# f-91ksd_r0.net
KiCad netlist of a schematic drawn in EAGLE
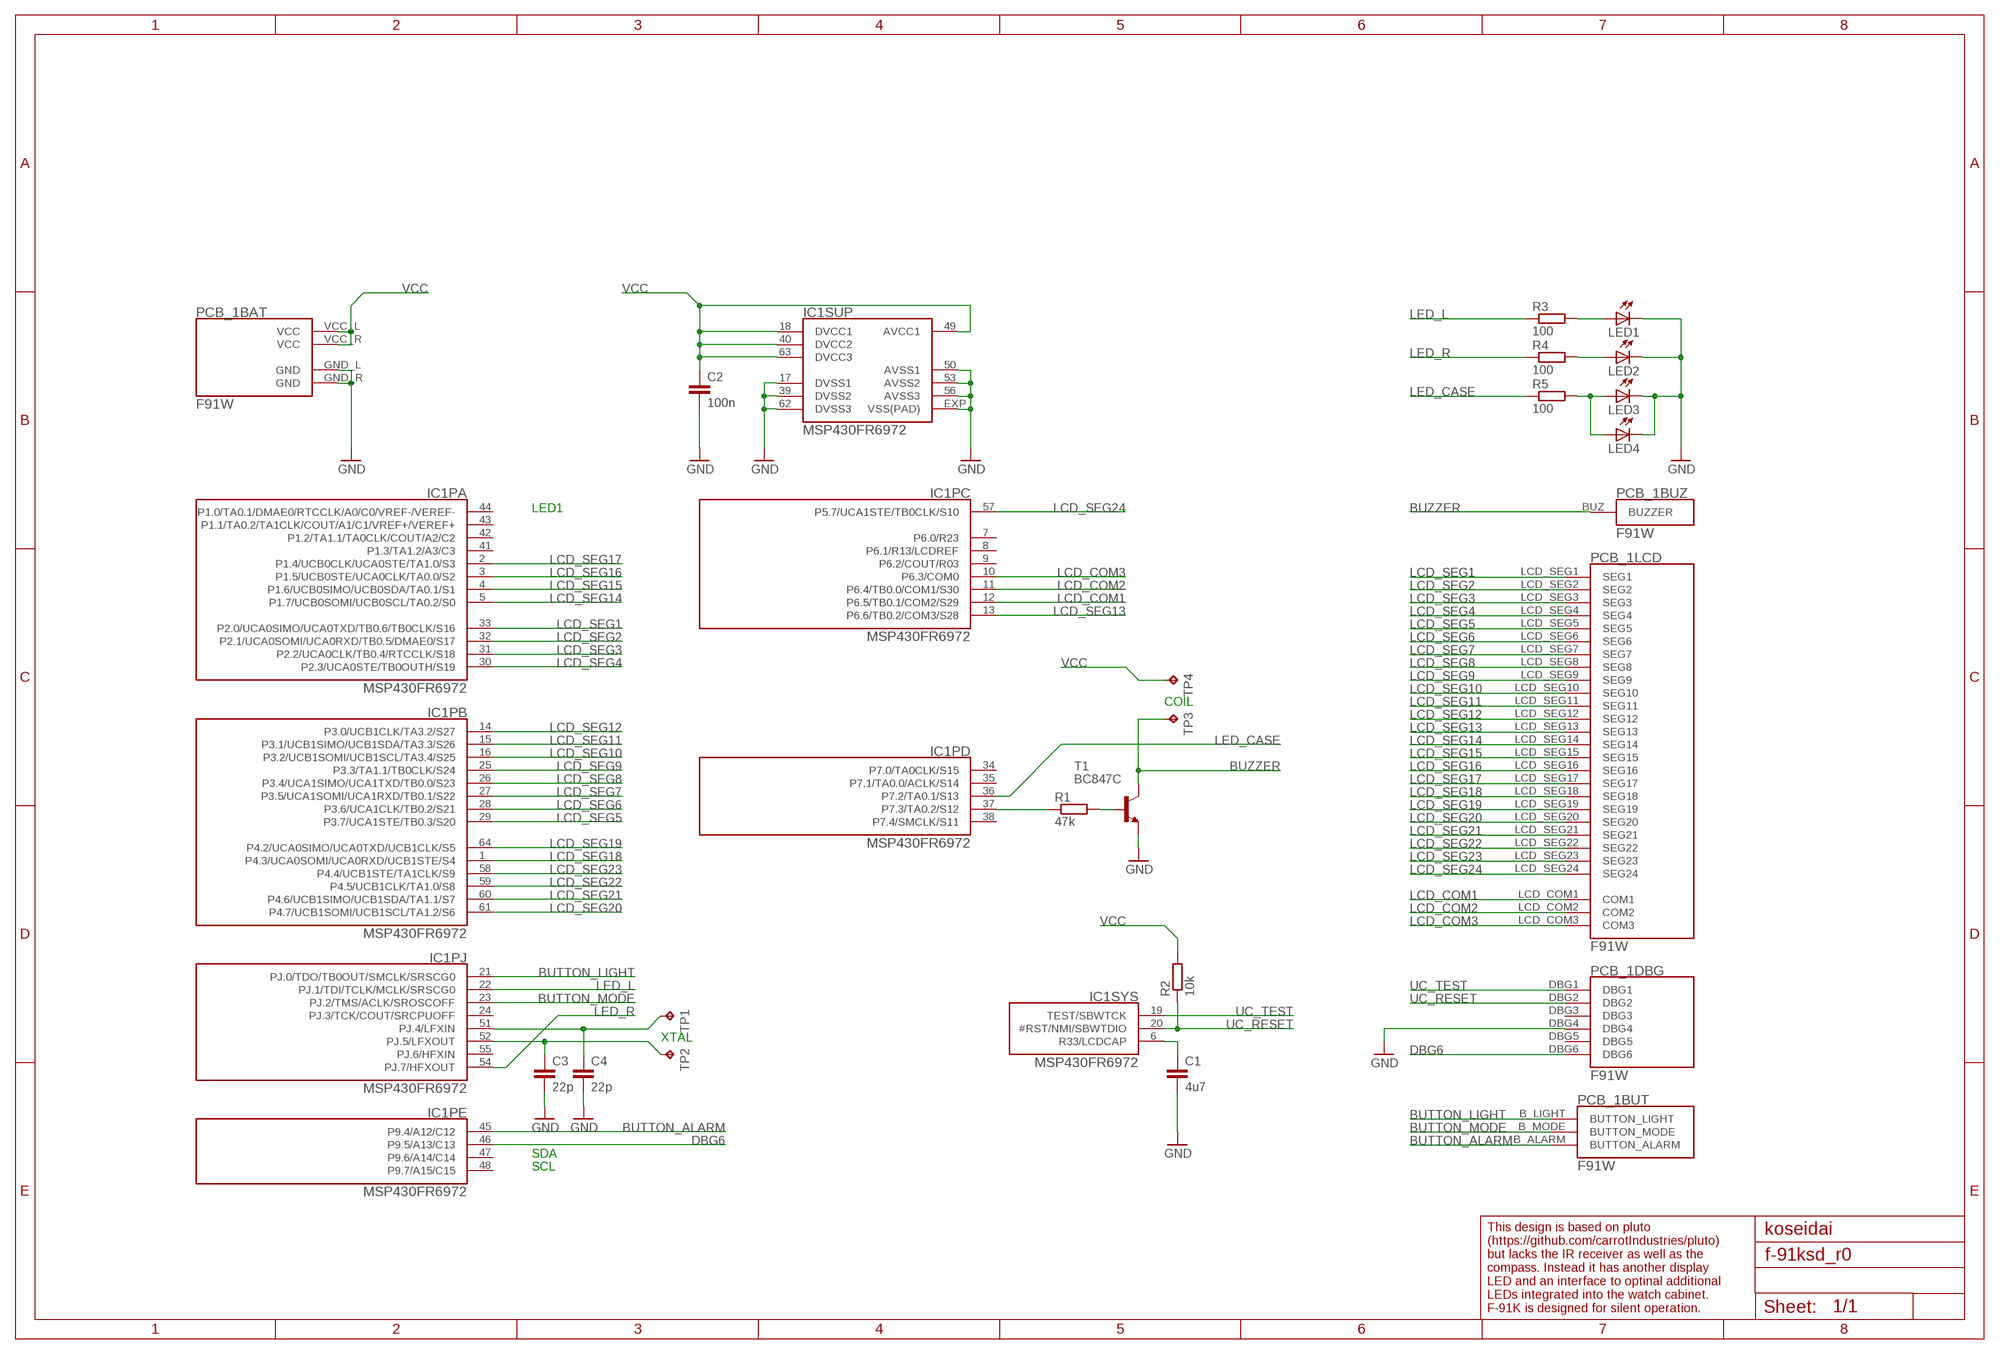
[diagram p0: schematic, sheet 1]

(export (version "E")
  (design (tool "Eeschema 10.0.6"))
  (components
    (comp (ref "C1")
      (value "4u7")
      (footprint "eagle-import:C0603-WW")
      (libsource (lib "eagle-import") (part "C-EUC0603-WW"))
    )
    (comp (ref "C2")
      (value "100n")
      (footprint "eagle-import:C0603-WW")
      (libsource (lib "eagle-import") (part "C-EUC0603-WW"))
    )
    (comp (ref "C3")
      (value "22p")
      (footprint "eagle-import:C0603-WW")
      (libsource (lib "eagle-import") (part "C-EUC0603-WW"))
    )
    (comp (ref "C4")
      (value "22p")
      (footprint "eagle-import:C0603-WW")
      (libsource (lib "eagle-import") (part "C-EUC0603-WW"))
    )
    (comp (ref "IC1")
      (value "MSP430FR6972")
      (footprint "eagle-import:QFN64-9X9")
      (libsource (lib "eagle-import") (part "MSP430FR6972"))
    )
    (comp (ref "LED1")
      (value "LEDCHIPLED_0805")
      (footprint "eagle-import:CHIPLED_0805")
      (libsource (lib "eagle-import") (part "LEDCHIPLED_0805"))
    )
    (comp (ref "LED2")
      (value "LEDCHIPLED_0805")
      (footprint "eagle-import:CHIPLED_0805")
      (libsource (lib "eagle-import") (part "LEDCHIPLED_0805"))
    )
    (comp (ref "LED3")
      (value "LEDCHIPLED_0603")
      (footprint "eagle-import:CHIPLED_0603")
      (libsource (lib "eagle-import") (part "LEDCHIPLED_0603"))
    )
    (comp (ref "LED4")
      (value "LEDCHIPLED_0603")
      (footprint "eagle-import:CHIPLED_0603")
      (libsource (lib "eagle-import") (part "LEDCHIPLED_0603"))
    )
    (comp (ref "PCB_1")
      (value "F91W")
      (footprint "eagle-import:F91W")
      (libsource (lib "eagle-import") (part "F91W"))
    )
    (comp (ref "R1")
      (value "47k")
      (footprint "eagle-import:R0603-WW")
      (libsource (lib "eagle-import") (part "R-EU_R0603-WW"))
    )
    (comp (ref "R2")
      (value "10k")
      (footprint "eagle-import:R0603-WW")
      (libsource (lib "eagle-import") (part "R-EU_R0603-WW"))
    )
    (comp (ref "R3")
      (value "100")
      (footprint "eagle-import:R0603-WW")
      (libsource (lib "eagle-import") (part "R-EU_R0603-WW"))
    )
    (comp (ref "R4")
      (value "100")
      (footprint "eagle-import:R0603-WW")
      (libsource (lib "eagle-import") (part "R-EU_R0603-WW"))
    )
    (comp (ref "R5")
      (value "100")
      (footprint "eagle-import:R0603-WW")
      (libsource (lib "eagle-import") (part "R-EU_R0603-WW"))
    )
    (comp (ref "T1")
      (value "BC847C")
      (footprint "eagle-import:SOT23-BEC")
      (libsource (lib "eagle-import") (part "-NPN-SOT23-BECBC847C"))
    )
    (comp (ref "TP1")
      (value "TPTP07SQ")
      (footprint "eagle-import:TP07SQ")
      (libsource (lib "eagle-import") (part "TPTP07SQ"))
    )
    (comp (ref "TP2")
      (value "TPTP07SQ")
      (footprint "eagle-import:TP07SQ")
      (libsource (lib "eagle-import") (part "TPTP07SQ"))
    )
    (comp (ref "TP3")
      (value "TPTP11SQ")
      (footprint "eagle-import:TP11SQ")
      (libsource (lib "eagle-import") (part "TPTP11SQ"))
    )
    (comp (ref "TP4")
      (value "TPTP11SQ")
      (footprint "eagle-import:TP11SQ")
      (libsource (lib "eagle-import") (part "TPTP11SQ"))
    )
  )
  (nets
    (net (code "1") (name "/BUTTON_ALARM") (class "Default")
      (node (ref "IC1") (pin "45") (pinfunction "P9.4/A12/C12_45") (pintype "bidirectional"))
      (node (ref "PCB_1") (pin "B_ALARM") (pinfunction "BUTTON_ALARM_B_ALARM") (pintype "output"))
    )
    (net (code "2") (name "/BUTTON_LIGHT") (class "Default")
      (node (ref "IC1") (pin "21") (pinfunction "PJ.0/TDO/TB0OUT/SMCLK/SRSCG0_21") (pintype "bidirectional"))
      (node (ref "PCB_1") (pin "B_LIGHT") (pinfunction "BUTTON_LIGHT_B_LIGHT") (pintype "output"))
    )
    (net (code "3") (name "/BUTTON_MODE") (class "Default")
      (node (ref "IC1") (pin "23") (pinfunction "PJ.2/TMS/ACLK/SROSCOFF_23") (pintype "bidirectional"))
      (node (ref "PCB_1") (pin "B_MODE") (pinfunction "BUTTON_MODE_B_MODE") (pintype "output"))
    )
    (net (code "4") (name "/BUZZER") (class "Default")
      (node (ref "PCB_1") (pin "BUZ") (pinfunction "BUZZER_BUZ") (pintype "passive"))
      (node (ref "T1") (pin "C") (pinfunction "C_C") (pintype "passive"))
      (node (ref "TP3") (pin "TP") (pinfunction "TP_TP") (pintype "input"))
    )
    (net (code "5") (name "/DBG6") (class "Default")
      (node (ref "IC1") (pin "46") (pinfunction "P9.5/A13/C13_46") (pintype "bidirectional"))
      (node (ref "PCB_1") (pin "DBG6") (pinfunction "DBG6_DBG6") (pintype "bidirectional"))
    )
    (net (code "6") (name "/LCD_COM1") (class "Default")
      (node (ref "IC1") (pin "12") (pinfunction "P6.5/TB0.1/COM2/S29_12") (pintype "bidirectional"))
      (node (ref "PCB_1") (pin "LCD_COM1") (pinfunction "COM1_LCD_COM1") (pintype "input"))
    )
    (net (code "7") (name "/LCD_COM2") (class "Default")
      (node (ref "IC1") (pin "11") (pinfunction "P6.4/TB0.0/COM1/S30_11") (pintype "bidirectional"))
      (node (ref "PCB_1") (pin "LCD_COM2") (pinfunction "COM2_LCD_COM2") (pintype "input"))
    )
    (net (code "8") (name "/LCD_COM3") (class "Default")
      (node (ref "IC1") (pin "10") (pinfunction "P6.3/COM0_10") (pintype "bidirectional"))
      (node (ref "PCB_1") (pin "LCD_COM3") (pinfunction "COM3_LCD_COM3") (pintype "input"))
    )
    (net (code "9") (name "/LCD_SEG1") (class "Default")
      (node (ref "IC1") (pin "33") (pinfunction "P2.0/UCA0SIMO/UCA0TXD/TB0.6/TB0CLK/S16_33") (pintype "bidirectional"))
      (node (ref "PCB_1") (pin "LCD_SEG1") (pinfunction "SEG1_LCD_SEG1") (pintype "input"))
    )
    (net (code "10") (name "/LCD_SEG2") (class "Default")
      (node (ref "IC1") (pin "32") (pinfunction "P2.1/UCA0SOMI/UCA0RXD/TB0.5/DMAE0/S17_32") (pintype "bidirectional"))
      (node (ref "PCB_1") (pin "LCD_SEG2") (pinfunction "SEG2_LCD_SEG2") (pintype "input"))
    )
    (net (code "11") (name "/LCD_SEG3") (class "Default")
      (node (ref "IC1") (pin "31") (pinfunction "P2.2/UCA0CLK/TB0.4/RTCCLK/S18_31") (pintype "bidirectional"))
      (node (ref "PCB_1") (pin "LCD_SEG3") (pinfunction "SEG3_LCD_SEG3") (pintype "input"))
    )
    (net (code "12") (name "/LCD_SEG4") (class "Default")
      (node (ref "IC1") (pin "30") (pinfunction "P2.3/UCA0STE/TB0OUTH/S19_30") (pintype "bidirectional"))
      (node (ref "PCB_1") (pin "LCD_SEG4") (pinfunction "SEG4_LCD_SEG4") (pintype "input"))
    )
    (net (code "13") (name "/LCD_SEG5") (class "Default")
      (node (ref "IC1") (pin "29") (pinfunction "P3.7/UCA1STE/TB0.3/S20_29") (pintype "bidirectional"))
      (node (ref "PCB_1") (pin "LCD_SEG5") (pinfunction "SEG5_LCD_SEG5") (pintype "input"))
    )
    (net (code "14") (name "/LCD_SEG6") (class "Default")
      (node (ref "IC1") (pin "28") (pinfunction "P3.6/UCA1CLK/TB0.2/S21_28") (pintype "bidirectional"))
      (node (ref "PCB_1") (pin "LCD_SEG6") (pinfunction "SEG6_LCD_SEG6") (pintype "input"))
    )
    (net (code "15") (name "/LCD_SEG7") (class "Default")
      (node (ref "IC1") (pin "27") (pinfunction "P3.5/UCA1SOMI/UCA1RXD/TB0.1/S22_27") (pintype "bidirectional"))
      (node (ref "PCB_1") (pin "LCD_SEG7") (pinfunction "SEG7_LCD_SEG7") (pintype "input"))
    )
    (net (code "16") (name "/LCD_SEG8") (class "Default")
      (node (ref "IC1") (pin "26") (pinfunction "P3.4/UCA1SIMO/UCA1TXD/TB0.0/S23_26") (pintype "bidirectional"))
      (node (ref "PCB_1") (pin "LCD_SEG8") (pinfunction "SEG8_LCD_SEG8") (pintype "input"))
    )
    (net (code "17") (name "/LCD_SEG9") (class "Default")
      (node (ref "IC1") (pin "25") (pinfunction "P3.3/TA1.1/TB0CLK/S24_25") (pintype "bidirectional"))
      (node (ref "PCB_1") (pin "LCD_SEG9") (pinfunction "SEG9_LCD_SEG9") (pintype "input"))
    )
    (net (code "18") (name "/LCD_SEG10") (class "Default")
      (node (ref "IC1") (pin "16") (pinfunction "P3.2/UCB1SOMI/UCB1SCL/TA3.4/S25_16") (pintype "bidirectional"))
      (node (ref "PCB_1") (pin "LCD_SEG10") (pinfunction "SEG10_LCD_SEG10") (pintype "input"))
    )
    (net (code "19") (name "/LCD_SEG11") (class "Default")
      (node (ref "IC1") (pin "15") (pinfunction "P3.1/UCB1SIMO/UCB1SDA/TA3.3/S26_15") (pintype "bidirectional"))
      (node (ref "PCB_1") (pin "LCD_SEG11") (pinfunction "SEG11_LCD_SEG11") (pintype "input"))
    )
    (net (code "20") (name "/LCD_SEG12") (class "Default")
      (node (ref "IC1") (pin "14") (pinfunction "P3.0/UCB1CLK/TA3.2/S27_14") (pintype "bidirectional"))
      (node (ref "PCB_1") (pin "LCD_SEG12") (pinfunction "SEG12_LCD_SEG12") (pintype "input"))
    )
    (net (code "21") (name "/LCD_SEG13") (class "Default")
      (node (ref "IC1") (pin "13") (pinfunction "P6.6/TB0.2/COM3/S28_13") (pintype "bidirectional"))
      (node (ref "PCB_1") (pin "LCD_SEG13") (pinfunction "SEG13_LCD_SEG13") (pintype "input"))
    )
    (net (code "22") (name "/LCD_SEG14") (class "Default")
      (node (ref "IC1") (pin "5") (pinfunction "P1.7/UCB0SOMI/UCB0SCL/TA0.2/S0_5") (pintype "bidirectional"))
      (node (ref "PCB_1") (pin "LCD_SEG14") (pinfunction "SEG14_LCD_SEG14") (pintype "input"))
    )
    (net (code "23") (name "/LCD_SEG15") (class "Default")
      (node (ref "IC1") (pin "4") (pinfunction "P1.6/UCB0SIMO/UCB0SDA/TA0.1/S1_4") (pintype "bidirectional"))
      (node (ref "PCB_1") (pin "LCD_SEG15") (pinfunction "SEG15_LCD_SEG15") (pintype "input"))
    )
    (net (code "24") (name "/LCD_SEG16") (class "Default")
      (node (ref "IC1") (pin "3") (pinfunction "P1.5/UCB0STE/UCA0CLK/TA0.0/S2_3") (pintype "bidirectional"))
      (node (ref "PCB_1") (pin "LCD_SEG16") (pinfunction "SEG16_LCD_SEG16") (pintype "input"))
    )
    (net (code "25") (name "/LCD_SEG17") (class "Default")
      (node (ref "IC1") (pin "2") (pinfunction "P1.4/UCB0CLK/UCA0STE/TA1.0/S3_2") (pintype "bidirectional"))
      (node (ref "PCB_1") (pin "LCD_SEG17") (pinfunction "SEG17_LCD_SEG17") (pintype "input"))
    )
    (net (code "26") (name "/LCD_SEG18") (class "Default")
      (node (ref "IC1") (pin "1") (pinfunction "P4.3/UCA0SOMI/UCA0RXD/UCB1STE/S4_1") (pintype "bidirectional"))
      (node (ref "PCB_1") (pin "LCD_SEG18") (pinfunction "SEG18_LCD_SEG18") (pintype "input"))
    )
    (net (code "27") (name "/LCD_SEG19") (class "Default")
      (node (ref "IC1") (pin "64") (pinfunction "P4.2/UCA0SIMO/UCA0TXD/UCB1CLK/S5_64") (pintype "bidirectional"))
      (node (ref "PCB_1") (pin "LCD_SEG19") (pinfunction "SEG19_LCD_SEG19") (pintype "input"))
    )
    (net (code "28") (name "/LCD_SEG20") (class "Default")
      (node (ref "IC1") (pin "61") (pinfunction "P4.7/UCB1SOMI/UCB1SCL/TA1.2/S6_61") (pintype "bidirectional"))
      (node (ref "PCB_1") (pin "LCD_SEG20") (pinfunction "SEG20_LCD_SEG20") (pintype "input"))
    )
    (net (code "29") (name "/LCD_SEG21") (class "Default")
      (node (ref "IC1") (pin "60") (pinfunction "P4.6/UCB1SIMO/UCB1SDA/TA1.1/S7_60") (pintype "bidirectional"))
      (node (ref "PCB_1") (pin "LCD_SEG21") (pinfunction "SEG21_LCD_SEG21") (pintype "input"))
    )
    (net (code "30") (name "/LCD_SEG22") (class "Default")
      (node (ref "IC1") (pin "59") (pinfunction "P4.5/UCB1CLK/TA1.0/S8_59") (pintype "bidirectional"))
      (node (ref "PCB_1") (pin "LCD_SEG22") (pinfunction "SEG22_LCD_SEG22") (pintype "input"))
    )
    (net (code "31") (name "/LCD_SEG23") (class "Default")
      (node (ref "IC1") (pin "58") (pinfunction "P4.4/UCB1STE/TA1CLK/S9_58") (pintype "bidirectional"))
      (node (ref "PCB_1") (pin "LCD_SEG23") (pinfunction "SEG23_LCD_SEG23") (pintype "input"))
    )
    (net (code "32") (name "/LCD_SEG24") (class "Default")
      (node (ref "IC1") (pin "57") (pinfunction "P5.7/UCA1STE/TB0CLK/S10_57") (pintype "bidirectional"))
      (node (ref "PCB_1") (pin "LCD_SEG24") (pinfunction "SEG24_LCD_SEG24") (pintype "input"))
    )
    (net (code "33") (name "/LED_CASE") (class "Default")
      (node (ref "IC1") (pin "36") (pinfunction "P7.2/TA0.1/S13_36") (pintype "bidirectional"))
      (node (ref "R5") (pin "1") (pinfunction "1_1") (pintype "passive"))
    )
    (net (code "34") (name "/LED_L") (class "Default")
      (node (ref "IC1") (pin "22") (pinfunction "PJ.1/TDI/TCLK/MCLK/SRSCG0_22") (pintype "bidirectional"))
      (node (ref "R3") (pin "1") (pinfunction "1_1") (pintype "passive"))
    )
    (net (code "35") (name "/LED_R") (class "Default")
      (node (ref "IC1") (pin "54") (pinfunction "PJ.7/HFXOUT_54") (pintype "bidirectional"))
      (node (ref "R4") (pin "1") (pinfunction "1_1") (pintype "passive"))
    )
    (net (code "36") (name "/UC_RESET") (class "Default")
      (node (ref "IC1") (pin "20") (pinfunction "#RST/NMI/SBWTDIO_20") (pintype "bidirectional"))
      (node (ref "PCB_1") (pin "DBG2") (pinfunction "DBG2_DBG2") (pintype "bidirectional"))
      (node (ref "R2") (pin "1") (pinfunction "1_1") (pintype "passive"))
    )
    (net (code "37") (name "/UC_TEST") (class "Default")
      (node (ref "IC1") (pin "19") (pinfunction "TEST/SBWTCK_19") (pintype "bidirectional"))
      (node (ref "PCB_1") (pin "DBG1") (pinfunction "DBG1_DBG1") (pintype "bidirectional"))
    )
    (net (code "38") (name "/VCC") (class "Default")
      (node (ref "C2") (pin "1") (pinfunction "1_1") (pintype "passive"))
      (node (ref "IC1") (pin "18") (pinfunction "DVCC1_18") (pintype "bidirectional"))
      (node (ref "IC1") (pin "40") (pinfunction "DVCC2_40") (pintype "bidirectional"))
      (node (ref "IC1") (pin "49") (pinfunction "AVCC1_49") (pintype "bidirectional"))
      (node (ref "IC1") (pin "63") (pinfunction "DVCC3_63") (pintype "bidirectional"))
      (node (ref "PCB_1") (pin "VCC_L") (pinfunction "VCC_VCC_L") (pintype "power_in"))
      (node (ref "PCB_1") (pin "VCC_R") (pinfunction "VCC_VCC_R") (pintype "power_in"))
      (node (ref "R2") (pin "2") (pinfunction "2_2") (pintype "passive"))
      (node (ref "TP4") (pin "TP") (pinfunction "TP_TP") (pintype "input"))
    )
    (net (code "39") (name "GND") (class "Default")
      (node (ref "C1") (pin "2") (pinfunction "2_2") (pintype "passive"))
      (node (ref "C2") (pin "2") (pinfunction "2_2") (pintype "passive"))
      (node (ref "C3") (pin "2") (pinfunction "2_2") (pintype "passive"))
      (node (ref "C4") (pin "2") (pinfunction "2_2") (pintype "passive"))
      (node (ref "IC1") (pin "17") (pinfunction "DVSS1_17") (pintype "bidirectional"))
      (node (ref "IC1") (pin "39") (pinfunction "DVSS2_39") (pintype "bidirectional"))
      (node (ref "IC1") (pin "50") (pinfunction "AVSS1_50") (pintype "bidirectional"))
      (node (ref "IC1") (pin "53") (pinfunction "AVSS2_53") (pintype "bidirectional"))
      (node (ref "IC1") (pin "56") (pinfunction "AVSS3_56") (pintype "bidirectional"))
      (node (ref "IC1") (pin "62") (pinfunction "DVSS3_62") (pintype "bidirectional"))
      (node (ref "IC1") (pin "EXP") (pinfunction "VSS(PAD)_EXP") (pintype "bidirectional"))
      (node (ref "LED1") (pin "C") (pinfunction "C_C") (pintype "passive"))
      (node (ref "LED2") (pin "C") (pinfunction "C_C") (pintype "passive"))
      (node (ref "LED3") (pin "C") (pinfunction "C_C") (pintype "passive"))
      (node (ref "LED4") (pin "C") (pinfunction "C_C") (pintype "passive"))
      (node (ref "PCB_1") (pin "DBG4") (pinfunction "DBG4_DBG4") (pintype "bidirectional"))
      (node (ref "PCB_1") (pin "GND_L") (pinfunction "GND_GND_L") (pintype "power_in"))
      (node (ref "PCB_1") (pin "GND_R") (pinfunction "GND_GND_R") (pintype "power_in"))
      (node (ref "T1") (pin "E") (pinfunction "E_E") (pintype "passive"))
    )
    (net (code "40") (name "Net-(IC1D-P7.3{slash}TA0.2{slash}S12)") (class "Default")
      (node (ref "IC1") (pin "37") (pinfunction "P7.3/TA0.2/S12_37") (pintype "bidirectional"))
      (node (ref "R1") (pin "1") (pinfunction "1_1") (pintype "passive"))
    )
    (net (code "41") (name "Net-(IC1F-PJ.4{slash}LFXIN)") (class "Default")
      (node (ref "C4") (pin "1") (pinfunction "1_1") (pintype "passive"))
      (node (ref "IC1") (pin "51") (pinfunction "PJ.4/LFXIN_51") (pintype "bidirectional"))
      (node (ref "TP1") (pin "TP") (pinfunction "TP_TP") (pintype "input"))
    )
    (net (code "42") (name "Net-(IC1F-PJ.5{slash}LFXOUT)") (class "Default")
      (node (ref "C3") (pin "1") (pinfunction "1_1") (pintype "passive"))
      (node (ref "IC1") (pin "52") (pinfunction "PJ.5/LFXOUT_52") (pintype "bidirectional"))
      (node (ref "TP2") (pin "TP") (pinfunction "TP_TP") (pintype "input"))
    )
    (net (code "43") (name "Net-(IC1H-R33{slash}LCDCAP)") (class "Default")
      (node (ref "C1") (pin "1") (pinfunction "1_1") (pintype "passive"))
      (node (ref "IC1") (pin "6") (pinfunction "R33/LCDCAP_6") (pintype "bidirectional"))
    )
    (net (code "44") (name "Net-(LED1-PadA)") (class "Default")
      (node (ref "LED1") (pin "A") (pinfunction "A_A") (pintype "passive"))
      (node (ref "R3") (pin "2") (pinfunction "2_2") (pintype "passive"))
    )
    (net (code "45") (name "Net-(LED2-PadA)") (class "Default")
      (node (ref "LED2") (pin "A") (pinfunction "A_A") (pintype "passive"))
      (node (ref "R4") (pin "2") (pinfunction "2_2") (pintype "passive"))
    )
    (net (code "46") (name "Net-(LED3-PadA)") (class "Default")
      (node (ref "LED3") (pin "A") (pinfunction "A_A") (pintype "passive"))
      (node (ref "LED4") (pin "A") (pinfunction "A_A") (pintype "passive"))
      (node (ref "R5") (pin "2") (pinfunction "2_2") (pintype "passive"))
    )
    (net (code "47") (name "Net-(R1-Pad2)") (class "Default")
      (node (ref "R1") (pin "2") (pinfunction "2_2") (pintype "passive"))
      (node (ref "T1") (pin "B") (pinfunction "B_B") (pintype "passive"))
    )
    (net (code "48") (name "unconnected-(IC1A-P1.0{slash}TA0.1{slash}DMAE0{slash}RTCCLK{slash}A0{slash}C0{slash}VREF-{slash}VEREF--Pad44)") (class "Default")
      (node (ref "IC1") (pin "44") (pinfunction "P1.0/TA0.1/DMAE0/RTCCLK/A0/C0/VREF-/VEREF-_44") (pintype "bidirectional"))
    )
    (net (code "49") (name "unconnected-(IC1A-P1.1{slash}TA0.2{slash}TA1CLK{slash}COUT{slash}A1{slash}C1{slash}VREF+{slash}VEREF+-Pad43)") (class "Default")
      (node (ref "IC1") (pin "43") (pinfunction "P1.1/TA0.2/TA1CLK/COUT/A1/C1/VREF+/VEREF+_43") (pintype "bidirectional"))
    )
    (net (code "50") (name "unconnected-(IC1A-P1.2{slash}TA1.1{slash}TA0CLK{slash}COUT{slash}A2{slash}C2-Pad42)") (class "Default")
      (node (ref "IC1") (pin "42") (pinfunction "P1.2/TA1.1/TA0CLK/COUT/A2/C2_42") (pintype "bidirectional"))
    )
    (net (code "51") (name "unconnected-(IC1A-P1.3{slash}TA1.2{slash}A3{slash}C3-Pad41)") (class "Default")
      (node (ref "IC1") (pin "41") (pinfunction "P1.3/TA1.2/A3/C3_41") (pintype "bidirectional"))
    )
    (net (code "52") (name "unconnected-(IC1C-P6.0{slash}R23-Pad7)") (class "Default")
      (node (ref "IC1") (pin "7") (pinfunction "P6.0/R23_7") (pintype "bidirectional"))
    )
    (net (code "53") (name "unconnected-(IC1C-P6.1{slash}R13{slash}LCDREF-Pad8)") (class "Default")
      (node (ref "IC1") (pin "8") (pinfunction "P6.1/R13/LCDREF_8") (pintype "bidirectional"))
    )
    (net (code "54") (name "unconnected-(IC1C-P6.2{slash}COUT{slash}R03-Pad9)") (class "Default")
      (node (ref "IC1") (pin "9") (pinfunction "P6.2/COUT/R03_9") (pintype "bidirectional"))
    )
    (net (code "55") (name "unconnected-(IC1D-P7.0{slash}TA0CLK{slash}S15-Pad34)") (class "Default")
      (node (ref "IC1") (pin "34") (pinfunction "P7.0/TA0CLK/S15_34") (pintype "bidirectional"))
    )
    (net (code "56") (name "unconnected-(IC1D-P7.1{slash}TA0.0{slash}ACLK{slash}S14-Pad35)") (class "Default")
      (node (ref "IC1") (pin "35") (pinfunction "P7.1/TA0.0/ACLK/S14_35") (pintype "bidirectional"))
    )
    (net (code "57") (name "unconnected-(IC1D-P7.4{slash}SMCLK{slash}S11-Pad38)") (class "Default")
      (node (ref "IC1") (pin "38") (pinfunction "P7.4/SMCLK/S11_38") (pintype "bidirectional"))
    )
    (net (code "58") (name "unconnected-(IC1E-P9.6{slash}A14{slash}C14-Pad47)") (class "Default")
      (node (ref "IC1") (pin "47") (pinfunction "P9.6/A14/C14_47") (pintype "bidirectional"))
    )
    (net (code "59") (name "unconnected-(IC1E-P9.7{slash}A15{slash}C15-Pad48)") (class "Default")
      (node (ref "IC1") (pin "48") (pinfunction "P9.7/A15/C15_48") (pintype "bidirectional"))
    )
    (net (code "60") (name "unconnected-(IC1F-PJ.3{slash}TCK{slash}COUT{slash}SRCPUOFF-Pad24)") (class "Default")
      (node (ref "IC1") (pin "24") (pinfunction "PJ.3/TCK/COUT/SRCPUOFF_24") (pintype "bidirectional"))
    )
    (net (code "61") (name "unconnected-(IC1F-PJ.6{slash}HFXIN-Pad55)") (class "Default")
      (node (ref "IC1") (pin "55") (pinfunction "PJ.6/HFXIN_55") (pintype "bidirectional"))
    )
    (net (code "62") (name "unconnected-(PCB_1-PadDBG3)") (class "Default")
      (node (ref "PCB_1") (pin "DBG3") (pinfunction "DBG3_DBG3") (pintype "bidirectional"))
    )
    (net (code "63") (name "unconnected-(PCB_1-PadDBG5)") (class "Default")
      (node (ref "PCB_1") (pin "DBG5") (pinfunction "DBG5_DBG5") (pintype "bidirectional"))
    )
  )
)
